# DB15F.net
KiCad netlist of a schematic drawn in Altium Designer
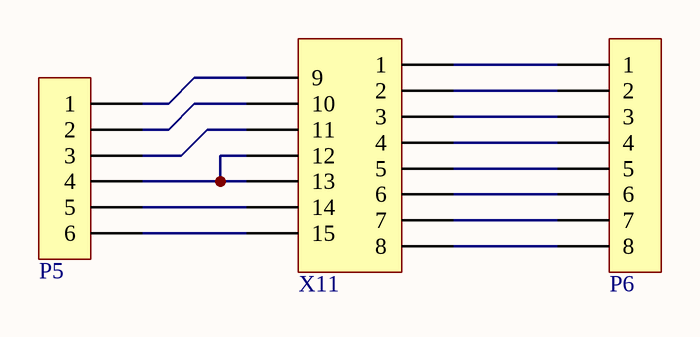
[diagram p0: DB15F.SchDoc]

(export (version "E")
  (design (tool "Eeschema 10.0.6"))
  (components
    (comp (ref "P5")
      (value "SIL-CONN-6")
      (footprint "SIL-CONN-6-R1")
      (libsource (lib "SchLib1") (part "SIL-CONN-6"))
    )
    (comp (ref "P6")
      (value "SIL-CONN-8")
      (footprint "SIL-CONN-8-R1")
      (libsource (lib "SchLib1") (part "SIL-CONN-8"))
    )
    (comp (ref "X11") (value "DB-15") (footprint "DB15F") (libsource (lib "SchLib1") (part "DB-15")))
  )
  (nets
    (net (code "1") (name "Net-(P5-Pad1)") (class "Default")
      (node (ref "P5") (pin "1") (pinfunction "1_1") (pintype "passive"))
      (node (ref "X11") (pin "9") (pinfunction "9_9") (pintype "passive"))
    )
    (net (code "2") (name "Net-(P5-Pad2)") (class "Default")
      (node (ref "P5") (pin "2") (pinfunction "2_2") (pintype "passive"))
      (node (ref "X11") (pin "10") (pinfunction "10_10") (pintype "passive"))
    )
    (net (code "3") (name "Net-(P5-Pad3)") (class "Default")
      (node (ref "P5") (pin "3") (pinfunction "3_3") (pintype "passive"))
      (node (ref "X11") (pin "11") (pinfunction "11_11") (pintype "passive"))
    )
    (net (code "4") (name "Net-(P5-Pad4)") (class "Default")
      (node (ref "P5") (pin "4") (pinfunction "4_4") (pintype "passive"))
      (node (ref "X11") (pin "12") (pinfunction "12_12") (pintype "passive"))
      (node (ref "X11") (pin "13") (pinfunction "13_13") (pintype "passive"))
    )
    (net (code "5") (name "Net-(P5-Pad5)") (class "Default")
      (node (ref "P5") (pin "5") (pinfunction "5_5") (pintype "passive"))
      (node (ref "X11") (pin "14") (pinfunction "14_14") (pintype "passive"))
    )
    (net (code "6") (name "Net-(P5-Pad6)") (class "Default")
      (node (ref "P5") (pin "6") (pinfunction "6_6") (pintype "passive"))
      (node (ref "X11") (pin "15") (pinfunction "15_15") (pintype "passive"))
    )
    (net (code "7") (name "Net-(P6-Pad1)") (class "Default")
      (node (ref "P6") (pin "1") (pinfunction "1_1") (pintype "passive"))
      (node (ref "X11") (pin "1") (pinfunction "1_1") (pintype "passive"))
    )
    (net (code "8") (name "Net-(P6-Pad2)") (class "Default")
      (node (ref "P6") (pin "2") (pinfunction "2_2") (pintype "passive"))
      (node (ref "X11") (pin "2") (pinfunction "2_2") (pintype "passive"))
    )
    (net (code "9") (name "Net-(P6-Pad3)") (class "Default")
      (node (ref "P6") (pin "3") (pinfunction "3_3") (pintype "passive"))
      (node (ref "X11") (pin "3") (pinfunction "3_3") (pintype "passive"))
    )
    (net (code "10") (name "Net-(P6-Pad4)") (class "Default")
      (node (ref "P6") (pin "4") (pinfunction "4_4") (pintype "passive"))
      (node (ref "X11") (pin "4") (pinfunction "4_4") (pintype "passive"))
    )
    (net (code "11") (name "Net-(P6-Pad5)") (class "Default")
      (node (ref "P6") (pin "5") (pinfunction "5_5") (pintype "passive"))
      (node (ref "X11") (pin "5") (pinfunction "5_5") (pintype "passive"))
    )
    (net (code "12") (name "Net-(P6-Pad6)") (class "Default")
      (node (ref "P6") (pin "6") (pinfunction "6_6") (pintype "passive"))
      (node (ref "X11") (pin "6") (pinfunction "6_6") (pintype "passive"))
    )
    (net (code "13") (name "Net-(P6-Pad7)") (class "Default")
      (node (ref "P6") (pin "7") (pinfunction "7_7") (pintype "passive"))
      (node (ref "X11") (pin "7") (pinfunction "7_7") (pintype "passive"))
    )
    (net (code "14") (name "Net-(P6-Pad8)") (class "Default")
      (node (ref "P6") (pin "8") (pinfunction "8_8") (pintype "passive"))
      (node (ref "X11") (pin "8") (pinfunction "8_8") (pintype "passive"))
    )
  )
)
